# USB_ULPI_Interface.net
KiCad netlist of a schematic drawn in Altium Designer
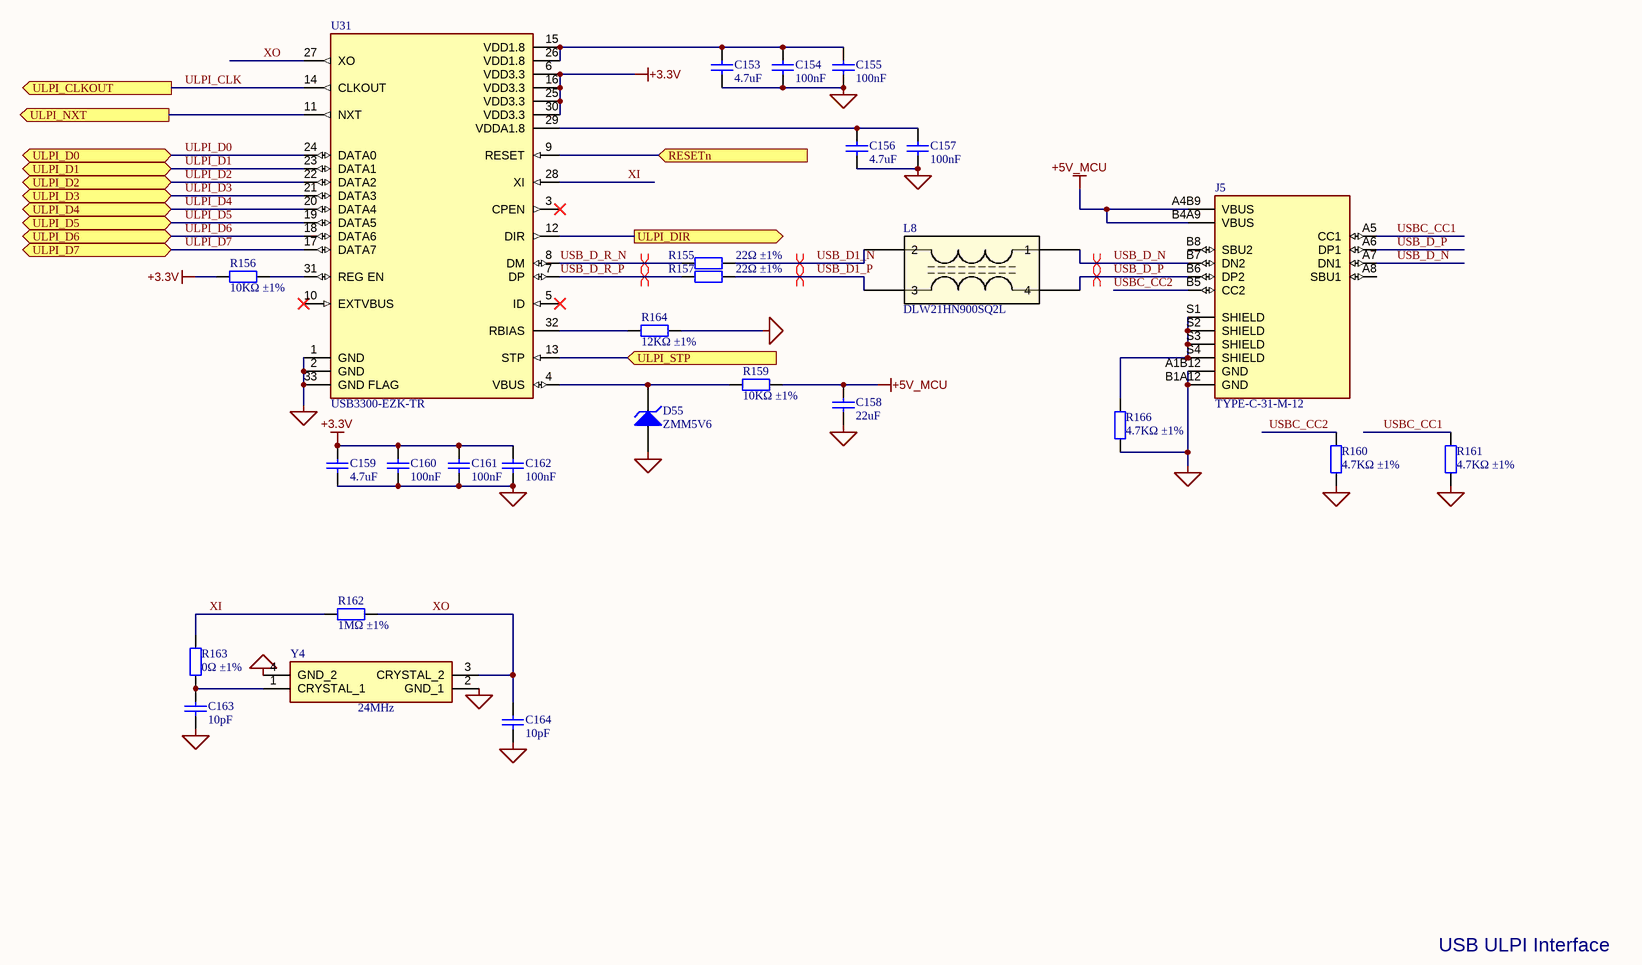
[diagram p0: USB_ULPI_Interface.SchDoc]

(export (version "E")
  (design (tool "Eeschema 10.0.6"))
  (components
    (comp (ref "C153")
      (value "4.7uF")
      (footprint "0603_C")
      (description "Chip capacitors")
      (fields
        (field (name "MANUFACTURER") "Samsung Electro-Mechanics")
        (field (name "PARTNUMBER") "CL10A475KO8NNNC")
      )
      (libsource (lib "Cap") (part "0603 4.7uF (475) 10% 16V"))
    )
    (comp (ref "C154")
      (value "100nF")
      (footprint "0603_C")
      (description "Chip capacitors")
      (fields (field (name "MANUFACTURER") "YAGEO") (field (name "PARTNUMBER") "CC0603KRX7R9BB104"))
      (libsource (lib "Cap") (part "0603 100nF (104) 10% 50V"))
    )
    (comp (ref "C155")
      (value "100nF")
      (footprint "0603_C")
      (description "Chip capacitors")
      (fields (field (name "MANUFACTURER") "YAGEO") (field (name "PARTNUMBER") "CC0603KRX7R9BB104"))
      (libsource (lib "Cap") (part "0603 100nF (104) 10% 50V"))
    )
    (comp (ref "C156")
      (value "4.7uF")
      (footprint "0603_C")
      (description "Chip capacitors")
      (fields
        (field (name "MANUFACTURER") "Samsung Electro-Mechanics")
        (field (name "PARTNUMBER") "CL10A475KO8NNNC")
      )
      (libsource (lib "Cap") (part "0603 4.7uF (475) 10% 16V"))
    )
    (comp (ref "C157")
      (value "100nF")
      (footprint "0603_C")
      (description "Chip capacitors")
      (fields (field (name "MANUFACTURER") "YAGEO") (field (name "PARTNUMBER") "CC0603KRX7R9BB104"))
      (libsource (lib "Cap") (part "0603 100nF (104) 10% 50V"))
    )
    (comp (ref "C158")
      (value "22uF")
      (footprint "0805_C")
      (description "Chip capacitors")
      (fields
        (field (name "MANUFACTURER") "Samsung Electro-Mechanics")
        (field (name "PARTNUMBER") "CL21A226MAQNNNE")
      )
      (libsource (lib "Cap") (part "0805 22uF (226) 20% 25V"))
    )
    (comp (ref "C159")
      (value "4.7uF")
      (footprint "0603_C")
      (description "Chip capacitors")
      (fields
        (field (name "MANUFACTURER") "Samsung Electro-Mechanics")
        (field (name "PARTNUMBER") "CL10A475KO8NNNC")
      )
      (libsource (lib "Cap") (part "0603 4.7uF (475) 10% 16V"))
    )
    (comp (ref "C160")
      (value "100nF")
      (footprint "0603_C")
      (description "Chip capacitors")
      (fields (field (name "MANUFACTURER") "YAGEO") (field (name "PARTNUMBER") "CC0603KRX7R9BB104"))
      (libsource (lib "Cap") (part "0603 100nF (104) 10% 50V"))
    )
    (comp (ref "C161")
      (value "100nF")
      (footprint "0603_C")
      (description "Chip capacitors")
      (fields (field (name "MANUFACTURER") "YAGEO") (field (name "PARTNUMBER") "CC0603KRX7R9BB104"))
      (libsource (lib "Cap") (part "0603 100nF (104) 10% 50V"))
    )
    (comp (ref "C162")
      (value "100nF")
      (footprint "0603_C")
      (description "Chip capacitors")
      (fields (field (name "MANUFACTURER") "YAGEO") (field (name "PARTNUMBER") "CC0603KRX7R9BB104"))
      (libsource (lib "Cap") (part "0603 100nF (104) 10% 50V"))
    )
    (comp (ref "C163")
      (value "10pF")
      (footprint "0402_C")
      (description "Chip capacitors")
      (fields
        (field (name "MANUFACTURER") "Samsung Electro-Mechanics")
        (field (name "MANUFACTURER PART NUMBER") "CL05C100JB5NNNC")
      )
      (libsource (lib "Cap") (part "0402 10pF (100) 5% 50V"))
    )
    (comp (ref "C164")
      (value "10pF")
      (footprint "0402_C")
      (description "Chip capacitors")
      (fields
        (field (name "MANUFACTURER") "Samsung Electro-Mechanics")
        (field (name "MANUFACTURER PART NUMBER") "CL05C100JB5NNNC")
      )
      (libsource (lib "Cap") (part "0402 10pF (100) 5% 50V"))
    )
    (comp (ref "D55")
      (value "ZMM5V6")
      (footprint "LL-34")
      (description "500mW - 0.1uA @ 1V 5.6V LL-34 Zener Diodes ROHS")
      (libsource (lib "Zener") (part "LL-34 ZMM5V6"))
    )
    (comp (ref "J5")
      (value "TYPE-C-31-M-12")
      (footprint "HRO_TYPE-C-31-M-12")
      (description "USB Connectors 24 Receptacle 1 8.94*7.3mm RoHS")
      (fields (field (name "MF") "HRO Electronics Co., Ltd."))
      (libsource (lib "Universal_CNC_Breakout") (part "TYPE-C-31-M-12"))
    )
    (comp (ref "L8")
      (value "DLW21HN900SQ2L")
      (footprint "DLW21HN121HQ2B")
      (description "90Ω@100MHz -40℃~+85℃ 350mΩ 50V 2 330mA 125V SMD-4P Common Mode Filters ROHS")
      (fields (field (name "MANUFACTURER") "Murata Electronics"))
      (libsource (lib "Sienci_Labs") (part "DLW21HN900SQ2L"))
    )
    (comp (ref "R155")
      (value "22Ω ±1%")
      (footprint "0603_R")
      (description "Chip resistor")
      (fields (field (name "MANUFACTURER") "Uniroyal Elec") (field (name "PARTNUMBER") "0603WAF220JT5E"))
      (libsource (lib "RES") (part "0603 22R (22R0) 1%"))
    )
    (comp (ref "R156")
      (value "10KΩ ±1%")
      (footprint "0603_R")
      (description "Chip resistor")
      (fields (field (name "MANUFACTURER") "Uniroyal Elec") (field (name "PARTNUMBER") "0603WAF1002T5E"))
      (libsource (lib "RES") (part "0603 10K (1002) 1%"))
    )
    (comp (ref "R157")
      (value "22Ω ±1%")
      (footprint "0603_R")
      (description "Chip resistor")
      (fields (field (name "MANUFACTURER") "Uniroyal Elec") (field (name "PARTNUMBER") "0603WAF220JT5E"))
      (libsource (lib "RES") (part "0603 22R (22R0) 1%"))
    )
    (comp (ref "R159")
      (value "10KΩ ±1%")
      (footprint "0603_R")
      (description "Chip resistor")
      (fields (field (name "MANUFACTURER") "Uniroyal Elec") (field (name "PARTNUMBER") "0603WAF1002T5E"))
      (libsource (lib "RES") (part "0603 10K (1002) 1%"))
    )
    (comp (ref "R160")
      (value "4.7KΩ ±1%")
      (footprint "0603_R")
      (description "Chip resistor")
      (fields (field (name "MANUFACTURER") "Uniroyal Elec") (field (name "PARTNUMBER") "0603WAF4701T5E"))
      (libsource (lib "RES") (part "0603 4.7K (4701) 1%"))
    )
    (comp (ref "R161")
      (value "4.7KΩ ±1%")
      (footprint "0603_R")
      (description "Chip resistor")
      (fields (field (name "MANUFACTURER") "Uniroyal Elec") (field (name "PARTNUMBER") "0603WAF4701T5E"))
      (libsource (lib "RES") (part "0603 4.7K (4701) 1%"))
    )
    (comp (ref "R162")
      (value "1MΩ ±1%")
      (footprint "0402_R")
      (description "Chip resistor")
      (fields
        (field (name "MANUFACTURER") "Uniroyal Elec")
        (field (name "MANUFACTURER PART NUMBER") "0402WGF1004TCE")
      )
      (libsource (lib "RES") (part "0402 1M (1004) 1%"))
    )
    (comp (ref "R163")
      (value "0Ω ±1%")
      (footprint "0402_R")
      (description "Chip resistor")
      (fields
        (field (name "MANUFACTURER") "Uniroyal Elec")
        (field (name "MANUFACTURER PART NUMBER") "0402WGF0000TCE")
      )
      (libsource (lib "RES") (part "0402 0R (0R0) 1%"))
    )
    (comp (ref "R164")
      (value "12KΩ ±1%")
      (footprint "0603_R")
      (description "Chip resistor")
      (fields (field (name "MANUFACTURER") "Uniroyal Elec") (field (name "PARTNUMBER") "0603WAF1202T5E"))
      (libsource (lib "RES") (part "0603 12K (1202) 1%"))
    )
    (comp (ref "R166")
      (value "4.7KΩ ±1%")
      (footprint "0603_R")
      (description "Chip resistor")
      (fields (field (name "MANUFACTURER") "Uniroyal Elec") (field (name "PARTNUMBER") "0603WAF4701T5E"))
      (libsource (lib "RES") (part "0603 4.7K (4701) 1%"))
    )
    (comp (ref "U31")
      (value "USB3300-EZK-TR")
      (footprint "FP-32QFN-3304-5X5B-MFG")
      (description "IC CONTROLLER USB 32QFN")
      (fields
        (field (name "MANUFACTURER") "Microchip")
        (field (name "OCTOPART") "https://octopart.com/usb3300-ezk-tr-microchip-24995444")
      )
      (libsource (lib "Altium Content Vault") (part "4aa10816561f241a170599044d3291b"))
    )
    (comp (ref "Y4")
      (value "24MHz")
      (footprint "YSX321SL")
      (description "24MHz SMD Crystal Resonator 20pF ±10ppm ±30ppm -40℃~+85℃ SMD3225-4P Crystals ROHS")
      (fields
        (field (name "MANUFACTURER") "Yangxing Tech")
        (field (name "MANUFACTURER PART NUMBER") "X322524MSB4SI")
      )
      (libsource (lib "Sienci_Labs") (part "X322525MSB4SI"))
    )
  )
  (nets
    (net (code "1") (name "+3.3V") (class "Default")
      (node (ref "C159") (pin "2") (pinfunction "2_2") (pintype "passive"))
      (node (ref "C160") (pin "2") (pinfunction "2_2") (pintype "passive"))
      (node (ref "C161") (pin "2") (pinfunction "2_2") (pintype "passive"))
      (node (ref "C162") (pin "2") (pinfunction "2_2") (pintype "passive"))
      (node (ref "R156") (pin "1") (pinfunction "1_1") (pintype "passive"))
      (node (ref "U31") (pin "16") (pinfunction "VDD3.3_16") (pintype "power_in"))
      (node (ref "U31") (pin "25") (pinfunction "VDD3.3_25") (pintype "power_in"))
      (node (ref "U31") (pin "30") (pinfunction "VDD3.3_30") (pintype "power_in"))
      (node (ref "U31") (pin "6") (pinfunction "VDD3.3_6") (pintype "power_in"))
    )
    (net (code "2") (name "+5V_MCU") (class "Default")
      (node (ref "C158") (pin "2") (pinfunction "2_2") (pintype "passive"))
      (node (ref "J5") (pin "A4B9") (pinfunction "VBUS_A4B9") (pintype "power_in"))
      (node (ref "J5") (pin "B4A9") (pinfunction "VBUS_B4A9") (pintype "power_in"))
      (node (ref "R159") (pin "2") (pinfunction "2_2") (pintype "passive"))
    )
    (net (code "3") (name "/RESETn") (class "Default")
      (node (ref "U31") (pin "9") (pinfunction "RESET_9") (pintype "input"))
    )
    (net (code "4") (name "/ULPI_CLK") (class "Default")
      (node (ref "U31") (pin "14") (pinfunction "CLKOUT_14") (pintype "output"))
    )
    (net (code "5") (name "/ULPI_D0") (class "Default")
      (node (ref "U31") (pin "24") (pinfunction "DATA0_24") (pintype "bidirectional"))
    )
    (net (code "6") (name "/ULPI_D1") (class "Default")
      (node (ref "U31") (pin "23") (pinfunction "DATA1_23") (pintype "bidirectional"))
    )
    (net (code "7") (name "/ULPI_D2") (class "Default")
      (node (ref "U31") (pin "22") (pinfunction "DATA2_22") (pintype "bidirectional"))
    )
    (net (code "8") (name "/ULPI_D3") (class "Default")
      (node (ref "U31") (pin "21") (pinfunction "DATA3_21") (pintype "bidirectional"))
    )
    (net (code "9") (name "/ULPI_D4") (class "Default")
      (node (ref "U31") (pin "20") (pinfunction "DATA4_20") (pintype "bidirectional"))
    )
    (net (code "10") (name "/ULPI_D5") (class "Default")
      (node (ref "U31") (pin "19") (pinfunction "DATA5_19") (pintype "bidirectional"))
    )
    (net (code "11") (name "/ULPI_D6") (class "Default")
      (node (ref "U31") (pin "18") (pinfunction "DATA6_18") (pintype "bidirectional"))
    )
    (net (code "12") (name "/ULPI_D7") (class "Default")
      (node (ref "U31") (pin "17") (pinfunction "DATA7_17") (pintype "bidirectional"))
    )
    (net (code "13") (name "/ULPI_DIR") (class "Default")
      (node (ref "U31") (pin "12") (pinfunction "DIR_12") (pintype "output"))
    )
    (net (code "14") (name "/ULPI_NXT") (class "Default")
      (node (ref "U31") (pin "11") (pinfunction "NXT_11") (pintype "output"))
    )
    (net (code "15") (name "/ULPI_STP") (class "Default")
      (node (ref "U31") (pin "13") (pinfunction "STP_13") (pintype "input"))
    )
    (net (code "16") (name "/USBC_CC1") (class "Default")
      (node (ref "J5") (pin "A5") (pinfunction "CC1_A5") (pintype "bidirectional"))
      (node (ref "R161") (pin "1") (pinfunction "1_1") (pintype "passive"))
    )
    (net (code "17") (name "/USBC_CC2") (class "Default")
      (node (ref "J5") (pin "B5") (pinfunction "CC2_B5") (pintype "bidirectional"))
      (node (ref "R160") (pin "1") (pinfunction "1_1") (pintype "passive"))
    )
    (net (code "18") (name "/USB_D1_N") (class "Default")
      (node (ref "L8") (pin "2") (pinfunction "2_2") (pintype "passive"))
      (node (ref "R155") (pin "2") (pinfunction "2_2") (pintype "passive"))
    )
    (net (code "19") (name "/USB_D1_P") (class "Default")
      (node (ref "L8") (pin "3") (pinfunction "3_3") (pintype "passive"))
      (node (ref "R157") (pin "2") (pinfunction "2_2") (pintype "passive"))
    )
    (net (code "20") (name "/USB_D_N") (class "Default")
      (node (ref "J5") (pin "A7") (pinfunction "DN1_A7") (pintype "bidirectional"))
      (node (ref "J5") (pin "B7") (pinfunction "DN2_B7") (pintype "bidirectional"))
      (node (ref "L8") (pin "1") (pinfunction "1_1") (pintype "passive"))
    )
    (net (code "21") (name "/USB_D_P") (class "Default")
      (node (ref "J5") (pin "A6") (pinfunction "DP1_A6") (pintype "bidirectional"))
      (node (ref "J5") (pin "B6") (pinfunction "DP2_B6") (pintype "bidirectional"))
      (node (ref "L8") (pin "4") (pinfunction "4_4") (pintype "passive"))
    )
    (net (code "22") (name "/USB_D_R_N") (class "Default")
      (node (ref "R155") (pin "1") (pinfunction "1_1") (pintype "passive"))
      (node (ref "U31") (pin "8") (pinfunction "DM_8") (pintype "bidirectional"))
    )
    (net (code "23") (name "/USB_D_R_P") (class "Default")
      (node (ref "R157") (pin "1") (pinfunction "1_1") (pintype "passive"))
      (node (ref "U31") (pin "7") (pinfunction "DP_7") (pintype "bidirectional"))
    )
    (net (code "24") (name "/XI") (class "Default")
      (node (ref "R162") (pin "1") (pinfunction "1_1") (pintype "passive"))
      (node (ref "R163") (pin "1") (pinfunction "1_1") (pintype "passive"))
      (node (ref "U31") (pin "28") (pinfunction "XI_28") (pintype "input"))
    )
    (net (code "25") (name "/XO") (class "Default")
      (node (ref "C164") (pin "2") (pinfunction "2_2") (pintype "passive"))
      (node (ref "R162") (pin "2") (pinfunction "2_2") (pintype "passive"))
      (node (ref "U31") (pin "27") (pinfunction "XO_27") (pintype "output"))
      (node (ref "Y4") (pin "3") (pinfunction "CRYSTAL_2_3") (pintype "passive"))
    )
    (net (code "26") (name "MCU_GND") (class "Default")
      (node (ref "C153") (pin "1") (pinfunction "1_1") (pintype "passive"))
      (node (ref "C154") (pin "1") (pinfunction "1_1") (pintype "passive"))
      (node (ref "C155") (pin "1") (pinfunction "1_1") (pintype "passive"))
      (node (ref "C156") (pin "1") (pinfunction "1_1") (pintype "passive"))
      (node (ref "C157") (pin "1") (pinfunction "1_1") (pintype "passive"))
      (node (ref "C158") (pin "1") (pinfunction "1_1") (pintype "passive"))
      (node (ref "C159") (pin "1") (pinfunction "1_1") (pintype "passive"))
      (node (ref "C160") (pin "1") (pinfunction "1_1") (pintype "passive"))
      (node (ref "C161") (pin "1") (pinfunction "1_1") (pintype "passive"))
      (node (ref "C162") (pin "1") (pinfunction "1_1") (pintype "passive"))
      (node (ref "C163") (pin "1") (pinfunction "1_1") (pintype "passive"))
      (node (ref "C164") (pin "1") (pinfunction "1_1") (pintype "passive"))
      (node (ref "D55") (pin "1") (pinfunction "A_1") (pintype "passive"))
      (node (ref "J5") (pin "A1B12") (pinfunction "GND_A1B12") (pintype "power_in"))
      (node (ref "J5") (pin "B1A12") (pinfunction "GND_B1A12") (pintype "power_in"))
      (node (ref "R160") (pin "2") (pinfunction "2_2") (pintype "passive"))
      (node (ref "R161") (pin "2") (pinfunction "2_2") (pintype "passive"))
      (node (ref "R164") (pin "2") (pinfunction "2_2") (pintype "passive"))
      (node (ref "R166") (pin "2") (pinfunction "2_2") (pintype "passive"))
      (node (ref "U31") (pin "1") (pinfunction "GND_1") (pintype "power_in"))
      (node (ref "U31") (pin "2") (pinfunction "GND_2") (pintype "power_in"))
      (node (ref "U31") (pin "33") (pinfunction "GND_FLAG_33") (pintype "power_in"))
      (node (ref "Y4") (pin "2") (pinfunction "GND_1_2") (pintype "passive"))
      (node (ref "Y4") (pin "4") (pinfunction "GND_2_4") (pintype "passive"))
    )
    (net (code "27") (name "Net-(C153-Pad2)") (class "Default")
      (node (ref "C153") (pin "2") (pinfunction "2_2") (pintype "passive"))
      (node (ref "C154") (pin "2") (pinfunction "2_2") (pintype "passive"))
      (node (ref "C155") (pin "2") (pinfunction "2_2") (pintype "passive"))
      (node (ref "U31") (pin "15") (pinfunction "VDD1.8_15") (pintype "power_in"))
      (node (ref "U31") (pin "26") (pinfunction "VDD1.8_26") (pintype "power_in"))
    )
    (net (code "28") (name "Net-(D55-K)") (class "Default")
      (node (ref "D55") (pin "2") (pinfunction "K_2") (pintype "passive"))
      (node (ref "R159") (pin "1") (pinfunction "1_1") (pintype "passive"))
      (node (ref "U31") (pin "4") (pinfunction "VBUS_4") (pintype "bidirectional"))
    )
    (net (code "29") (name "Net-(J5-SHIELD-PadS1)") (class "Default")
      (node (ref "J5") (pin "S1") (pinfunction "SHIELD_S1") (pintype "passive"))
      (node (ref "J5") (pin "S2") (pinfunction "SHIELD_S2") (pintype "passive"))
      (node (ref "J5") (pin "S3") (pinfunction "SHIELD_S3") (pintype "passive"))
      (node (ref "J5") (pin "S4") (pinfunction "SHIELD_S4") (pintype "passive"))
      (node (ref "R166") (pin "1") (pinfunction "1_1") (pintype "passive"))
    )
    (net (code "30") (name "Net-(U31-RBIAS)") (class "Default")
      (node (ref "R164") (pin "1") (pinfunction "1_1") (pintype "passive"))
      (node (ref "U31") (pin "32") (pinfunction "RBIAS_32") (pintype "power_in"))
    )
    (net (code "31") (name "Net-(U31-REG_EN)") (class "Default")
      (node (ref "R156") (pin "2") (pinfunction "2_2") (pintype "passive"))
      (node (ref "U31") (pin "31") (pinfunction "REG_EN_31") (pintype "bidirectional"))
    )
    (net (code "32") (name "Net-(U31-VDDA1.8)") (class "Default")
      (node (ref "C156") (pin "2") (pinfunction "2_2") (pintype "passive"))
      (node (ref "C157") (pin "2") (pinfunction "2_2") (pintype "passive"))
      (node (ref "U31") (pin "29") (pinfunction "VDDA1.8_29") (pintype "power_in"))
    )
    (net (code "33") (name "Net-(Y4-CRYSTAL_1)") (class "Default")
      (node (ref "C163") (pin "2") (pinfunction "2_2") (pintype "passive"))
      (node (ref "R163") (pin "2") (pinfunction "2_2") (pintype "passive"))
      (node (ref "Y4") (pin "1") (pinfunction "CRYSTAL_1_1") (pintype "passive"))
    )
    (net (code "34") (name "unconnected-(J5-SBU1-PadA8)") (class "Default")
      (node (ref "J5") (pin "A8") (pinfunction "SBU1_A8") (pintype "bidirectional"))
    )
    (net (code "35") (name "unconnected-(J5-SBU2-PadB8)") (class "Default")
      (node (ref "J5") (pin "B8") (pinfunction "SBU2_B8") (pintype "bidirectional"))
    )
    (net (code "36") (name "unconnected-(U31-CPEN-Pad3)") (class "Default")
      (node (ref "U31") (pin "3") (pinfunction "CPEN_3") (pintype "output+no_connect"))
    )
    (net (code "37") (name "unconnected-(U31-EXTVBUS-Pad10)") (class "Default")
      (node (ref "U31") (pin "10") (pinfunction "EXTVBUS_10") (pintype "input+no_connect"))
    )
    (net (code "38") (name "unconnected-(U31-ID-Pad5)") (class "Default")
      (node (ref "U31") (pin "5") (pinfunction "ID_5") (pintype "input+no_connect"))
    )
  )
)
